# Schematic_Rev1.net
KiCad netlist of a schematic drawn in Altium Designer
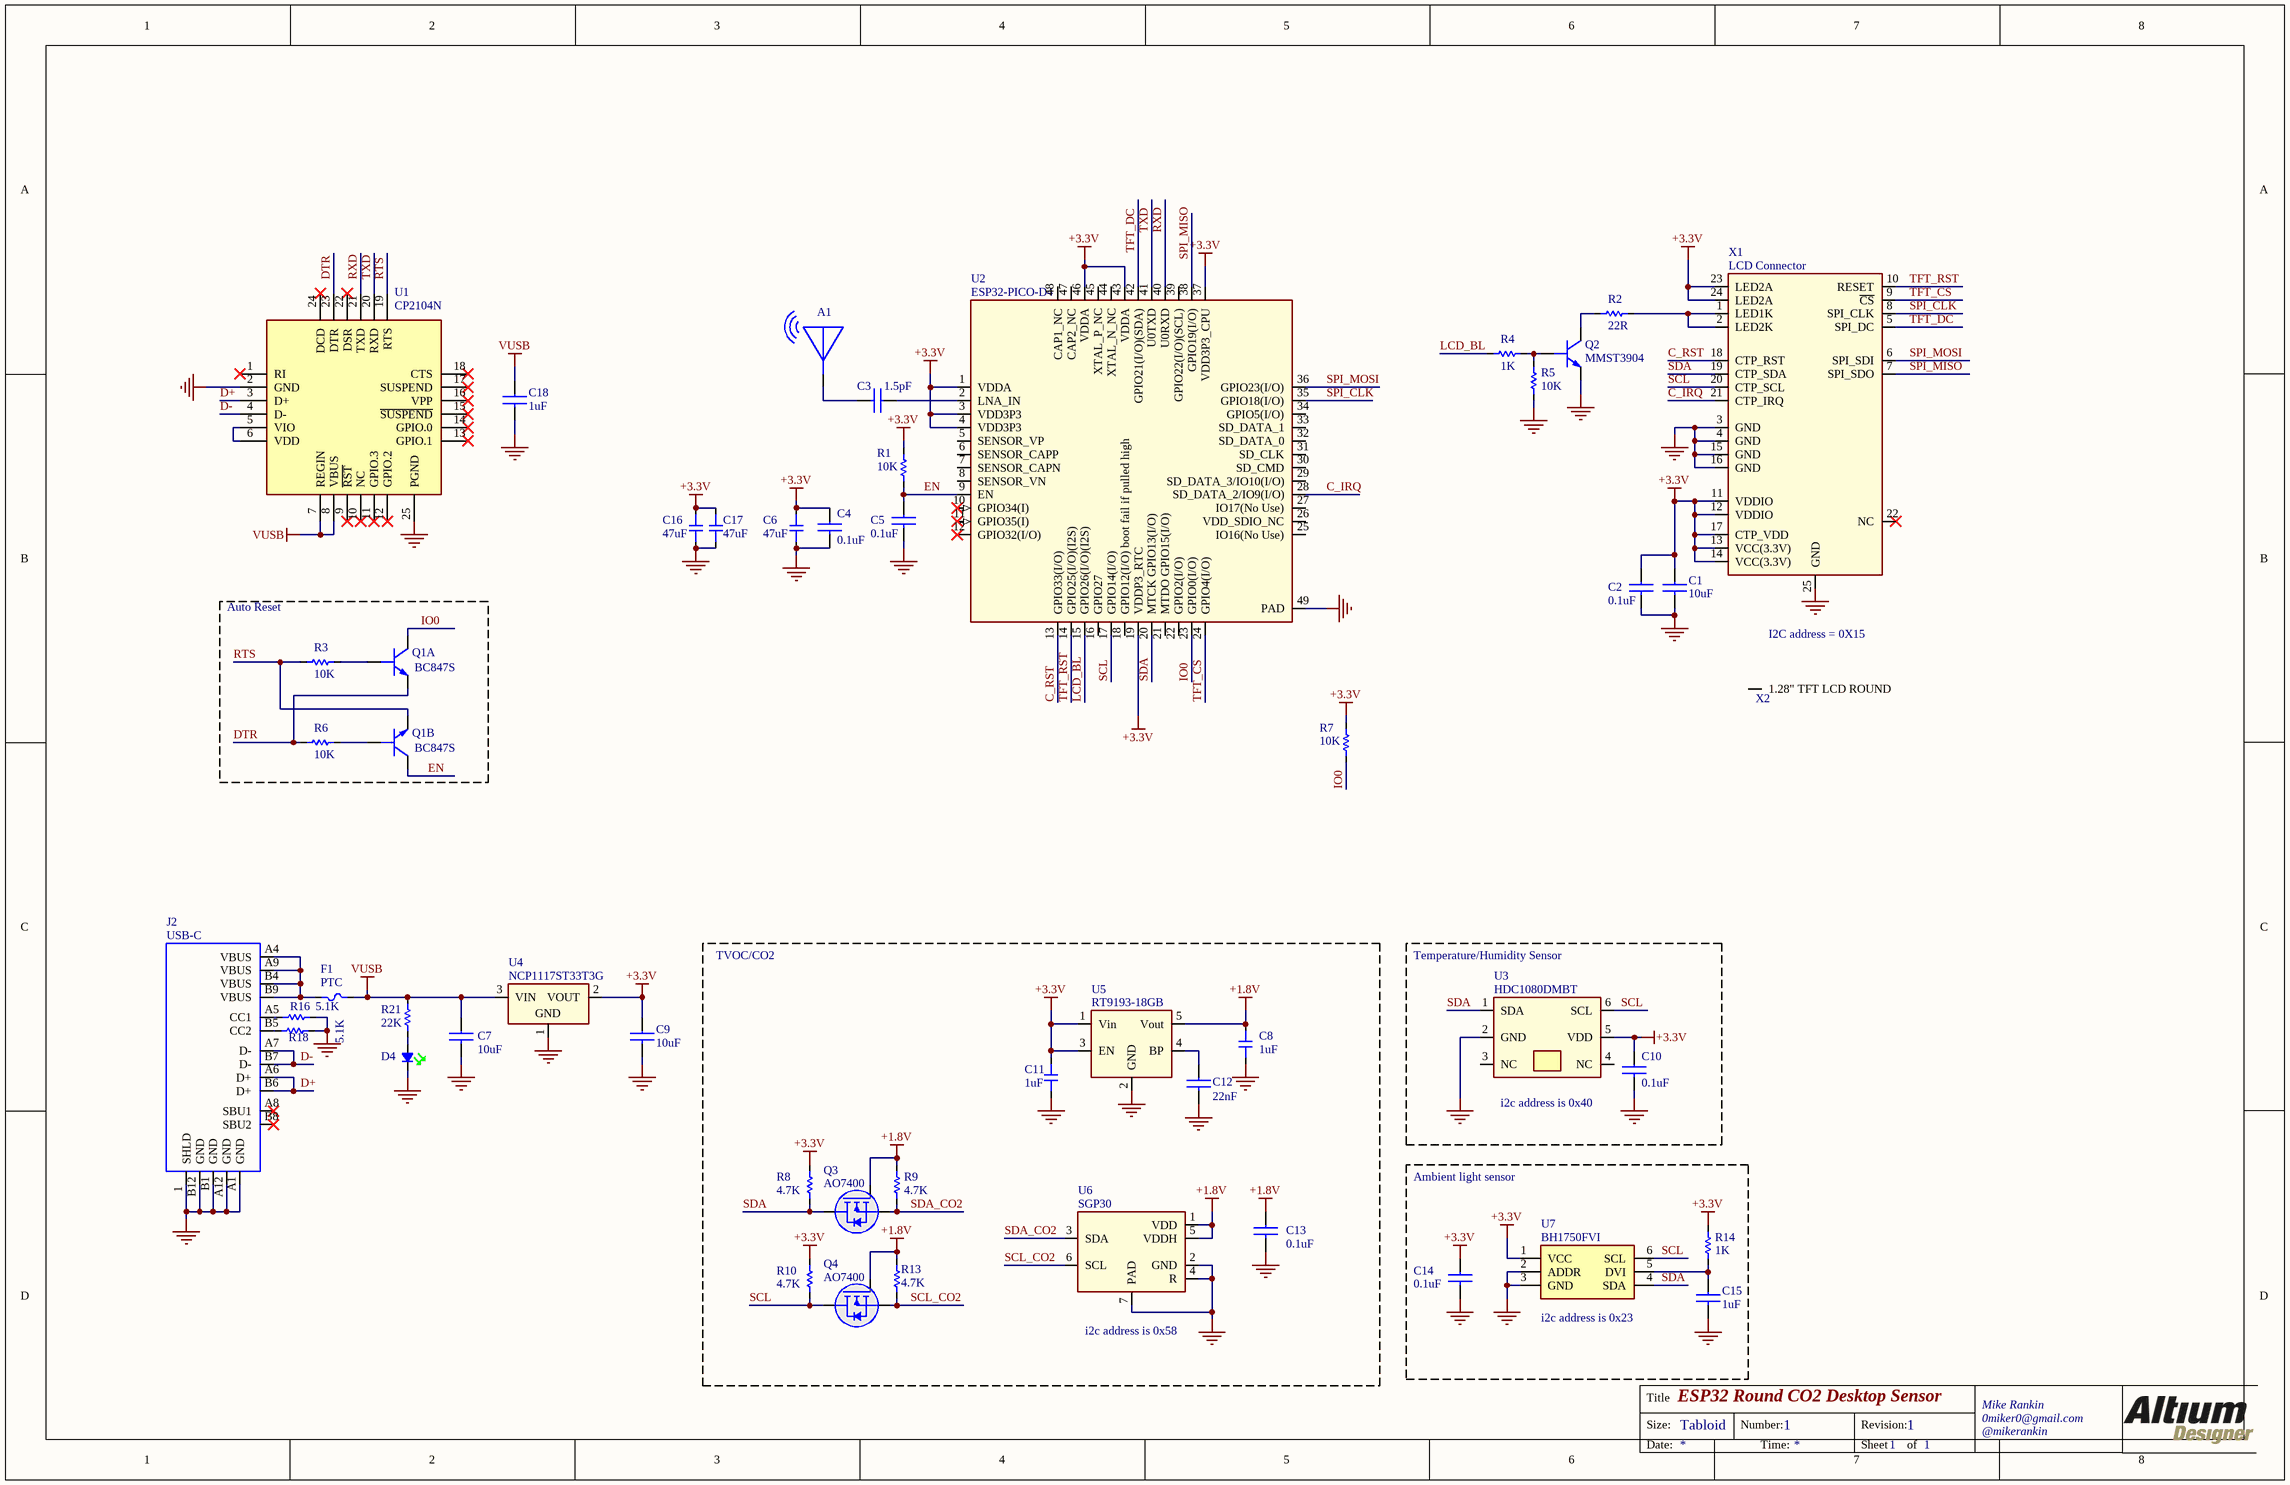
[diagram p0: Schematic_Rev1.SchDoc]

(export (version "E")
  (design (tool "Eeschema 10.0.6"))
  (components
    (comp (ref "A1")
      (value "Antenna_Chip_1")
      (footprint "NN01-102")
      (description "Antenna Chip 2.4Gig")
      (fields (field (name "MANUFACTURER") "Rainsun") (field (name "PART_NUMBER") "C99665"))
      (libsource (lib "MAR") (part "Antenna_Chip_1"))
    )
    (comp (ref "C1")
      (value "10uF")
      (footprint "CAPC2012X140N")
      (description "CAP 10uF 0805")
      (libsource (lib "MAR") (part "CAP_0805"))
    )
    (comp (ref "C2")
      (value "0.1uF")
      (footprint "CAPC1005X56N")
      (description "CAP 0.1uF 0402")
      (libsource (lib "MAR") (part "CAP_0402"))
    )
    (comp (ref "C3")
      (value "1.5pF")
      (footprint "CAPC1005X56N")
      (description "CAP 1.5pF 0402")
      (libsource (lib "MAR") (part "CAP_0402"))
    )
    (comp (ref "C4")
      (value "0.1uF")
      (footprint "CAPC1005X56N")
      (description "CAP 0.1uF 0402")
      (libsource (lib "MAR") (part "CAP_0402"))
    )
    (comp (ref "C5")
      (value "0.1uF")
      (footprint "CAPC1005X56N")
      (description "CAP 0.1uF 0402")
      (libsource (lib "MAR") (part "CAP_0402"))
    )
    (comp (ref "C6")
      (value "47uF")
      (footprint "CAPC3225X160N")
      (description "CAP 47uF 1210")
      (libsource (lib "MAR") (part "CAP_1210"))
    )
    (comp (ref "C7")
      (value "10uF")
      (footprint "CAPC2012X140N")
      (description "CAP 10uF 0805")
      (libsource (lib "MAR") (part "CAP_0805"))
    )
    (comp (ref "C8")
      (value "1uF")
      (footprint "CAPC1608X09L")
      (description "CAP 1uF 0603")
      (libsource (lib "MAR") (part "CAP_0603"))
    )
    (comp (ref "C9")
      (value "10uF")
      (footprint "CAPC2012X140N")
      (description "CAP 10uF 0805")
      (libsource (lib "MAR") (part "CAP_0805"))
    )
    (comp (ref "C10")
      (value "0.1uF")
      (footprint "CAPC1005X56N")
      (description "CAP 0.1uF 0402")
      (libsource (lib "MAR") (part "CAP_0402"))
    )
    (comp (ref "C11")
      (value "1uF")
      (footprint "CAPC1608X09L")
      (description "CAP 1uF 0603")
      (libsource (lib "MAR") (part "CAP_0603"))
    )
    (comp (ref "C12")
      (value "22nF")
      (footprint "CAPC1005X56N")
      (description "CAP 22nF 0402")
      (libsource (lib "MAR") (part "CAP_0402"))
    )
    (comp (ref "C13")
      (value "0.1uF")
      (footprint "CAPC1005X56N")
      (description "CAP 0.1uF 0402")
      (libsource (lib "MAR") (part "CAP_0402"))
    )
    (comp (ref "C14")
      (value "0.1uF")
      (footprint "CAPC1005X56N")
      (description "CAP 0.1uF 0402")
      (libsource (lib "MAR") (part "CAP_0402"))
    )
    (comp (ref "C15")
      (value "1uF")
      (footprint "CAPC1005X56N")
      (description "CAP 1uF 16V 0402")
      (libsource (lib "") (part "CAP_0603_1"))
    )
    (comp (ref "C16")
      (value "47uF")
      (footprint "CAPC3225X160N")
      (description "CAP 47uF 1210")
      (libsource (lib "MAR") (part "CAP_1210"))
    )
    (comp (ref "C17")
      (value "47uF")
      (footprint "CAPC3225X160N")
      (description "CAP 47uF 1210")
      (libsource (lib "MAR") (part "CAP_1210"))
    )
    (comp (ref "C18")
      (value "1uF")
      (footprint "CAPC1005X56N")
      (description "CAP 1uF 16V 0402")
      (libsource (lib "") (part "CAP_0603_1"))
    )
    (comp (ref "D4")
      (value "Green Led")
      (footprint "LED1005X40N-Green")
      (description "LED Green 0402")
      (fields (field (name "PART_NUMBER") "C74338"))
      (libsource (lib "MAR") (part "LED_0402_SMALL_GREEN"))
    )
    (comp (ref "F1")
      (value "PTC")
      (footprint "RESC1608X06L (0603 FOOTPRINT)")
      (description "PTC FUSE 0.5mA hold, 1A trip 0603")
      (fields (field (name "MANUFACTURER") "JDT Fuse") (field (name "PART_NUMBER") "C2982257"))
      (libsource (lib "MAR") (part "PTC_FUSE_0603"))
    )
    (comp (ref "J2")
      (value "USB-C")
      (footprint "TYPE-C-31-M-12")
      (description "CONN RECPT USB-C")
      (fields (field (name "MANUFACTURER") "KHE") (field (name "PART_NUMBER") "C165948"))
      (libsource (lib "MAR") (part "USB-C"))
    )
    (comp (ref "Q1")
      (value "BC847S")
      (footprint "SOT65P210X110-6N")
      (description "TRANS 2NPN 44V 0.1A SC-70-6")
      (fields (field (name "MANUFACTURER") "Changjiang") (field (name "PART_NUMBER") "BC847S"))
      (libsource (lib "MAR") (part "BC847S"))
    )
    (comp (ref "Q2")
      (value "MMST3904")
      (footprint "SC-70")
      (description "TRANSISTOR NPN GP 40V SC-70")
      (fields (field (name "MANUFACTURER") "Changjiang") (field (name "PART_NUMBER") "C54879"))
      (libsource (lib "MAR") (part "MMST3904"))
    )
    (comp (ref "Q3")
      (value "AO7400")
      (footprint "SC-70")
      (description "MOSFET N-CH 20V 4A SC70-3")
      (fields (field (name "MANUFACTURER") "VBSemi Elec"))
      (libsource (lib "MAR") (part "AO7400"))
    )
    (comp (ref "Q4")
      (value "AO7400")
      (footprint "SC-70")
      (description "MOSFET N-CH 20V 4A SC70-3")
      (fields (field (name "MANUFACTURER") "VBSemi Elec"))
      (libsource (lib "MAR") (part "AO7400"))
    )
    (comp (ref "R1")
      (value "10K")
      (footprint "RESC1005X40L")
      (description "RES 10K 0402")
      (libsource (lib "MAR") (part "RES_0402"))
    )
    (comp (ref "R2")
      (value "22R")
      (footprint "RESC1005X40L")
      (description "RES 22R 0402")
      (libsource (lib "MAR") (part "RES_0402"))
    )
    (comp (ref "R3")
      (value "10K")
      (footprint "RESC1005X40L")
      (description "RES 10K 0402")
      (libsource (lib "MAR") (part "RES_0402"))
    )
    (comp (ref "R4")
      (value "1K")
      (footprint "RESC1005X40L")
      (description "RES 1K 0402")
      (libsource (lib "MAR") (part "RES_0402"))
    )
    (comp (ref "R5")
      (value "10K")
      (footprint "RESC1005X40L")
      (description "RES 10K 0402")
      (libsource (lib "MAR") (part "RES_0402"))
    )
    (comp (ref "R6")
      (value "10K")
      (footprint "RESC1005X40L")
      (description "RES 10K 0402")
      (libsource (lib "MAR") (part "RES_0402"))
    )
    (comp (ref "R7")
      (value "10K")
      (footprint "RESC1005X40L")
      (description "RES 10K 0402")
      (libsource (lib "MAR") (part "RES_0402"))
    )
    (comp (ref "R8")
      (value "4.7K")
      (footprint "RESC1005X40L (0402 FOOTPRINT)")
      (description "RES 4.7K 0402")
      (libsource (lib "MAR") (part "RES_0402"))
    )
    (comp (ref "R9")
      (value "4.7K")
      (footprint "RESC1005X40L (0402 FOOTPRINT)")
      (description "RES 4.7K 0402")
      (libsource (lib "MAR") (part "RES_0402"))
    )
    (comp (ref "R10")
      (value "4.7K")
      (footprint "RESC1005X40L (0402 FOOTPRINT)")
      (description "RES 4.7K 0402")
      (libsource (lib "MAR") (part "RES_0402"))
    )
    (comp (ref "R13")
      (value "4.7K")
      (footprint "RESC1005X40L (0402 FOOTPRINT)")
      (description "RES 4.7K 0402")
      (libsource (lib "MAR") (part "RES_0402"))
    )
    (comp (ref "R14")
      (value "1K")
      (footprint "RESC1005X40L (0402 FOOTPRINT)")
      (description "RES 1K 0402")
      (libsource (lib "MAR") (part "RES_0402"))
    )
    (comp (ref "R16")
      (value "5.1K")
      (footprint "RESC1005X40L")
      (description "RES 5.1K 0402")
      (libsource (lib "MAR") (part "RES_0603"))
    )
    (comp (ref "R18")
      (value "5.1K")
      (footprint "RESC1005X40L")
      (description "RES 5.1K 0402")
      (libsource (lib "MAR") (part "RES_0603"))
    )
    (comp (ref "R21")
      (value "22K")
      (footprint "RESC1005X40L")
      (description "RES 22K 0402")
      (libsource (lib "MAR") (part "RES_0603"))
    )
    (comp (ref "U1")
      (value "CP2104N")
      (footprint "24-QFN")
      (description "IC BRIDGE USB TO UART 24QFN")
      (fields (field (name "MANUFACTURER") "Silicon Labs") (field (name "PART_NUMBER") "C47742"))
      (libsource (lib "MAR") (part "CP2104N"))
    )
    (comp (ref "U2")
      (value "ESP32-PICO-D4")
      (footprint "QFN48_NEWEST 0.5mm pitch")
      (description "WIFI/Bluetooth, QFN-48 7x7")
      (fields (field (name "MANUFACTURER") "Espressif") (field (name "PART_NUMBER") "C193707"))
      (libsource (lib "MAR") (part "ESP32-PICO-D4"))
    )
    (comp (ref "U3")
      (value "HDC1080DMBT")
      (footprint "HDC1080")
      (description "Humidity/Temperature Sensor")
      (fields (field (name "MANUFACTURER") "Texas Instruments") (field (name "PART_NUMBER") "C82227"))
      (libsource (lib "MAR") (part "HDC1080DMBT"))
    )
    (comp (ref "U4")
      (value "NCP1117ST33T3G")
      (footprint "SOT230P700X180-4N")
      (description "IC REG LDO 1.0A 3.3V SOT-223")
      (fields (field (name "MANUFACTURER") "On Semi") (field (name "PART_NUMBER") "C26537"))
      (libsource (lib "MAR") (part "NCP1117ST33T3G"))
    )
    (comp (ref "U5")
      (value "1.8V LDO")
      (footprint "SOT95P280X144-5N")
      (description "IC REG LDO 1.8V 300mA SOT23-5")
      (fields (field (name "MANUFACTURER") "Richtek USA") (field (name "PART_NUMBER") "RT9193-18GB"))
      (libsource (lib "MAR") (part "RT9193-18GB"))
    )
    (comp (ref "U6")
      (value "SGP30")
      (footprint "DFN-6 (2.45mm X 2.45mm)")
      (description "TVOC/CO2 Sensor")
      (fields (field (name "MANUFACTURER") "Sensirion AG") (field (name "PART_NUMBER") "SGP30-2.5K"))
      (libsource (lib "MAR") (part "SGP30"))
    )
    (comp (ref "U7")
      (value "BH1750FVI")
      (footprint "WSOF-6")
      (description "Optical Sensor Ambient I2C 6-SMD")
      (fields (field (name "MANUFACTURER") "Rohm") (field (name "PART_NUMBER") "C78960"))
      (libsource (lib "MAR") (part "BH1750FVI"))
    )
    (comp (ref "X1")
      (value "LCD Connector")
      (footprint "BM10NB(0.8)-24DS-0.4V(51)")
      (description "FFC, FPC 24 pin 0.4mm Connector for 1.28\" TFT")
      (fields (field (name "PART_NUMBER") "BM10NB(0.8)-24DS-0.4V(51)") (field (name "MANUFACTURER") "Hirose"))
      (libsource (lib "MAR") (part "FFC, FPC 24 pin 0.5mm Con 1.28{dblquote} TFT"))
    )
    (comp (ref "X2")
      (value "TFT_1.28 inch")
      (description "1.28 INCH TFT GLASS ROUND")
      (fields (field (name "PART_NUMBER") "ER-TFT1.28-2") (field (name "MANUFACTURER") "BuyDisplay"))
      (libsource (lib "MAR") (part "TFT_GLASS 1.28 Inch Round"))
    )
  )
  (nets
    (net (code "1") (name "+1.8V") (class "Default")
      (node (ref "C13") (pin "1") (pinfunction "1_1") (pintype "passive"))
      (node (ref "C8") (pin "1") (pintype "passive"))
      (node (ref "Q3") (pin "1") (pinfunction "G_1") (pintype "passive"))
      (node (ref "Q4") (pin "1") (pinfunction "G_1") (pintype "passive"))
      (node (ref "R13") (pin "2") (pintype "passive"))
      (node (ref "R9") (pin "2") (pintype "passive"))
      (node (ref "U5") (pin "5") (pinfunction "Vout_5") (pintype "passive"))
      (node (ref "U6") (pin "1") (pinfunction "VDD_1") (pintype "power_in"))
      (node (ref "U6") (pin "5") (pinfunction "VDDH_5") (pintype "power_in"))
    )
    (net (code "2") (name "+3.3V") (class "Default")
      (node (ref "C1") (pin "1") (pinfunction "1_1") (pintype "passive"))
      (node (ref "C10") (pin "1") (pinfunction "1_1") (pintype "passive"))
      (node (ref "C11") (pin "1") (pintype "passive"))
      (node (ref "C14") (pin "1") (pinfunction "1_1") (pintype "passive"))
      (node (ref "C16") (pin "1") (pintype "passive"))
      (node (ref "C17") (pin "1") (pintype "passive"))
      (node (ref "C2") (pin "1") (pinfunction "1_1") (pintype "passive"))
      (node (ref "C4") (pin "1") (pinfunction "1_1") (pintype "passive"))
      (node (ref "C6") (pin "1") (pintype "passive"))
      (node (ref "C9") (pin "1") (pinfunction "1_1") (pintype "passive"))
      (node (ref "R1") (pin "1") (pintype "passive"))
      (node (ref "R10") (pin "2") (pintype "passive"))
      (node (ref "R14") (pin "2") (pintype "passive"))
      (node (ref "R7") (pin "1") (pintype "passive"))
      (node (ref "R8") (pin "2") (pintype "passive"))
      (node (ref "U2") (pin "1") (pinfunction "VDDA_1") (pintype "power_in"))
      (node (ref "U2") (pin "19") (pinfunction "VDDP3_RTC_19") (pintype "passive"))
      (node (ref "U2") (pin "3") (pinfunction "VDD3P3_3") (pintype "power_in"))
      (node (ref "U2") (pin "37") (pinfunction "VDD3P3_CPU_37") (pintype "power_in"))
      (node (ref "U2") (pin "4") (pinfunction "VDD3P3_4") (pintype "power_in"))
      (node (ref "U2") (pin "43") (pinfunction "VDDA_43") (pintype "power_in"))
      (node (ref "U2") (pin "46") (pinfunction "VDDA_46") (pintype "power_in"))
      (node (ref "U3") (pin "5") (pinfunction "VDD_5") (pintype "power_in"))
      (node (ref "U4") (pin "2") (pinfunction "VOUT_2") (pintype "power_in"))
      (node (ref "U5") (pin "1") (pinfunction "Vin_1") (pintype "passive"))
      (node (ref "U5") (pin "3") (pinfunction "EN_3") (pintype "passive"))
      (node (ref "U7") (pin "1") (pinfunction "VCC_1") (pintype "power_in"))
      (node (ref "X1") (pin "11") (pinfunction "VDDIO_11") (pintype "power_in"))
      (node (ref "X1") (pin "12") (pinfunction "VDDIO_12") (pintype "power_in"))
      (node (ref "X1") (pin "13") (pinfunction "VCC(3.3V)_13") (pintype "power_in"))
      (node (ref "X1") (pin "14") (pinfunction "VCC(3.3V)_14") (pintype "open_emitter"))
      (node (ref "X1") (pin "17") (pinfunction "CTP_VDD_17") (pintype "power_in"))
      (node (ref "X1") (pin "23") (pinfunction "LED2A_23") (pintype "passive"))
      (node (ref "X1") (pin "24") (pinfunction "LED2A_24") (pintype "passive"))
    )
    (net (code "3") (name "/C_IRQ") (class "Default")
      (node (ref "U2") (pin "28") (pinfunction "SD_DATA_2/IO9(I/O)_28") (pintype "passive"))
      (node (ref "X1") (pin "21") (pinfunction "CTP_IRQ_21") (pintype "passive"))
    )
    (net (code "4") (name "/C_RST") (class "Default")
      (node (ref "U2") (pin "13") (pinfunction "GPIO33(I/O)_13") (pintype "passive"))
      (node (ref "X1") (pin "18") (pinfunction "CTP_RST_18") (pintype "passive"))
    )
    (net (code "5") (name "/D+") (class "Default")
      (node (ref "J2") (pin "A6") (pinfunction "D+_A6") (pintype "power_in"))
      (node (ref "J2") (pin "B6") (pinfunction "D+_B6") (pintype "power_in"))
      (node (ref "U1") (pin "3") (pinfunction "D+_3") (pintype "passive"))
    )
    (net (code "6") (name "/D-") (class "Default")
      (node (ref "J2") (pin "A7") (pinfunction "D-_A7") (pintype "power_in"))
      (node (ref "J2") (pin "B7") (pinfunction "D-_B7") (pintype "power_in"))
      (node (ref "U1") (pin "4") (pinfunction "D-_4") (pintype "passive"))
    )
    (net (code "7") (name "/DTR") (class "Default")
      (node (ref "Q1") (pin "1") (pinfunction "E1_1") (pintype "passive"))
      (node (ref "R6") (pin "2") (pintype "passive"))
      (node (ref "U1") (pin "23") (pinfunction "DTR_23") (pintype "passive"))
    )
    (net (code "8") (name "/EN") (class "Default")
      (node (ref "C5") (pin "1") (pinfunction "1_1") (pintype "passive"))
      (node (ref "Q1") (pin "3") (pinfunction "C2_3") (pintype "passive"))
      (node (ref "R1") (pin "2") (pintype "passive"))
      (node (ref "U2") (pin "9") (pinfunction "EN_9") (pintype "passive"))
    )
    (net (code "9") (name "/IO0") (class "Default")
      (node (ref "Q1") (pin "6") (pinfunction "C1_6") (pintype "passive"))
      (node (ref "R7") (pin "2") (pintype "passive"))
      (node (ref "U2") (pin "23") (pinfunction "GPIO0(I/O)_23") (pintype "passive"))
    )
    (net (code "10") (name "/LCD_BL") (class "Default")
      (node (ref "R4") (pin "1") (pintype "passive"))
      (node (ref "U2") (pin "15") (pinfunction "GPIO26(I/O)(I2S)_15") (pintype "passive"))
    )
    (net (code "11") (name "/RTS") (class "Default")
      (node (ref "Q1") (pin "4") (pinfunction "E2_4") (pintype "passive"))
      (node (ref "R3") (pin "2") (pintype "passive"))
      (node (ref "U1") (pin "19") (pinfunction "RTS_19") (pintype "passive"))
    )
    (net (code "12") (name "/RXD") (class "Default")
      (node (ref "U1") (pin "21") (pinfunction "TXD_21") (pintype "passive"))
      (node (ref "U2") (pin "40") (pinfunction "U0RXD_40") (pintype "passive"))
    )
    (net (code "13") (name "/SCL") (class "Default")
      (node (ref "Q4") (pin "3") (pinfunction "D_3") (pintype "passive"))
      (node (ref "R10") (pin "1") (pintype "passive"))
      (node (ref "U2") (pin "17") (pinfunction "GPIO14(I/O)_17") (pintype "passive"))
      (node (ref "U3") (pin "6") (pinfunction "SCL_6") (pintype "passive"))
      (node (ref "U7") (pin "6") (pinfunction "SCL_6") (pintype "passive"))
      (node (ref "X1") (pin "20") (pinfunction "CTP_SCL_20") (pintype "passive"))
    )
    (net (code "14") (name "/SCL_CO2") (class "Default")
      (node (ref "Q4") (pin "2") (pinfunction "S_2") (pintype "passive"))
      (node (ref "R13") (pin "1") (pintype "passive"))
      (node (ref "U6") (pin "6") (pinfunction "SCL_6") (pintype "passive"))
    )
    (net (code "15") (name "/SDA") (class "Default")
      (node (ref "Q3") (pin "3") (pinfunction "D_3") (pintype "passive"))
      (node (ref "R8") (pin "1") (pintype "passive"))
      (node (ref "U2") (pin "20") (pinfunction "MTCK_GPIO13(I/O)_20") (pintype "passive"))
      (node (ref "U3") (pin "1") (pinfunction "SDA_1") (pintype "passive"))
      (node (ref "U7") (pin "4") (pinfunction "SDA_4") (pintype "passive"))
      (node (ref "X1") (pin "19") (pinfunction "CTP_SDA_19") (pintype "passive"))
    )
    (net (code "16") (name "/SDA_CO2") (class "Default")
      (node (ref "Q3") (pin "2") (pinfunction "S_2") (pintype "passive"))
      (node (ref "R9") (pin "1") (pintype "passive"))
      (node (ref "U6") (pin "3") (pinfunction "SDA_3") (pintype "passive"))
    )
    (net (code "17") (name "/SPI_CLK") (class "Default")
      (node (ref "U2") (pin "35") (pinfunction "GPIO18(I/O)_35") (pintype "passive"))
      (node (ref "X1") (pin "8") (pinfunction "SPI_CLK_8") (pintype "passive"))
    )
    (net (code "18") (name "/SPI_MISO") (class "Default")
      (node (ref "U2") (pin "38") (pinfunction "GPIO19(I/O)_38") (pintype "passive"))
      (node (ref "X1") (pin "7") (pinfunction "SPI_SDO_7") (pintype "passive"))
    )
    (net (code "19") (name "/SPI_MOSI") (class "Default")
      (node (ref "U2") (pin "36") (pinfunction "GPIO23(I/O)_36") (pintype "passive"))
      (node (ref "X1") (pin "6") (pinfunction "SPI_SDI_6") (pintype "passive"))
    )
    (net (code "20") (name "/TFT_CS") (class "Default")
      (node (ref "U2") (pin "24") (pinfunction "GPIO4(I/O)_24") (pintype "passive"))
      (node (ref "X1") (pin "9") (pinfunction "~{CS}_9") (pintype "passive"))
    )
    (net (code "21") (name "/TFT_DC") (class "Default")
      (node (ref "U2") (pin "42") (pinfunction "GPIO21(I/O)(SDA)_42") (pintype "passive"))
      (node (ref "X1") (pin "5") (pinfunction "SPI_DC_5") (pintype "passive"))
    )
    (net (code "22") (name "/TFT_RST") (class "Default")
      (node (ref "U2") (pin "14") (pinfunction "GPIO25(I/O)(I2S)_14") (pintype "passive"))
      (node (ref "X1") (pin "10") (pinfunction "RESET_10") (pintype "passive"))
    )
    (net (code "23") (name "/TXD") (class "Default")
      (node (ref "U1") (pin "20") (pinfunction "RXD_20") (pintype "passive"))
      (node (ref "U2") (pin "41") (pinfunction "U0TXD_41") (pintype "passive"))
    )
    (net (code "24") (name "GND") (class "Default")
      (node (ref "C1") (pin "2") (pinfunction "2_2") (pintype "passive"))
      (node (ref "C10") (pin "2") (pinfunction "2_2") (pintype "passive"))
      (node (ref "C11") (pin "2") (pintype "passive"))
      (node (ref "C12") (pin "2") (pinfunction "2_2") (pintype "passive"))
      (node (ref "C13") (pin "2") (pinfunction "2_2") (pintype "passive"))
      (node (ref "C14") (pin "2") (pinfunction "2_2") (pintype "passive"))
      (node (ref "C15") (pin "2") (pinfunction "2_2") (pintype "passive"))
      (node (ref "C16") (pin "2") (pintype "passive"))
      (node (ref "C17") (pin "2") (pintype "passive"))
      (node (ref "C18") (pin "2") (pinfunction "2_2") (pintype "passive"))
      (node (ref "C2") (pin "2") (pinfunction "2_2") (pintype "passive"))
      (node (ref "C4") (pin "2") (pinfunction "2_2") (pintype "passive"))
      (node (ref "C5") (pin "2") (pinfunction "2_2") (pintype "passive"))
      (node (ref "C6") (pin "2") (pintype "passive"))
      (node (ref "C7") (pin "2") (pinfunction "2_2") (pintype "passive"))
      (node (ref "C8") (pin "2") (pintype "passive"))
      (node (ref "C9") (pin "2") (pinfunction "2_2") (pintype "passive"))
      (node (ref "D4") (pin "1") (pintype "passive"))
      (node (ref "J2") (pin "1") (pinfunction "SHLD_1") (pintype "power_in"))
      (node (ref "J2") (pin "A1") (pinfunction "GND_A1") (pintype "power_in"))
      (node (ref "J2") (pin "A12") (pinfunction "GND_A12") (pintype "power_in"))
      (node (ref "J2") (pin "B1") (pinfunction "GND_B1") (pintype "power_in"))
      (node (ref "J2") (pin "B12") (pinfunction "GND_B12") (pintype "passive"))
      (node (ref "Q2") (pin "2") (pinfunction "E_2") (pintype "passive"))
      (node (ref "R16") (pin "2") (pintype "passive"))
      (node (ref "R18") (pin "2") (pintype "passive"))
      (node (ref "R5") (pin "2") (pintype "passive"))
      (node (ref "U1") (pin "2") (pinfunction "GND_2") (pintype "power_in"))
      (node (ref "U1") (pin "25") (pinfunction "PGND_25") (pintype "passive"))
      (node (ref "U2") (pin "49") (pinfunction "PAD_49") (pintype "power_in"))
      (node (ref "U3") (pin "2") (pinfunction "GND_2") (pintype "power_in"))
      (node (ref "U4") (pin "1") (pinfunction "GND_1") (pintype "power_in"))
      (node (ref "U5") (pin "2") (pinfunction "GND_2") (pintype "power_in"))
      (node (ref "U6") (pin "2") (pinfunction "GND_2") (pintype "power_in"))
      (node (ref "U6") (pin "4") (pinfunction "R_4") (pintype "passive"))
      (node (ref "U6") (pin "7") (pinfunction "PAD_7") (pintype "passive"))
      (node (ref "U7") (pin "2") (pinfunction "ADDR_2") (pintype "passive"))
      (node (ref "U7") (pin "3") (pinfunction "GND_3") (pintype "power_in"))
      (node (ref "X1") (pin "15") (pinfunction "GND_15") (pintype "power_in"))
      (node (ref "X1") (pin "16") (pinfunction "GND_16") (pintype "power_in"))
      (node (ref "X1") (pin "25") (pinfunction "GND_25") (pintype "power_in"))
      (node (ref "X1") (pin "3") (pinfunction "GND_3") (pintype "power_in"))
      (node (ref "X1") (pin "4") (pinfunction "GND_4") (pintype "power_in"))
    )
    (net (code "25") (name "Net-(A1-Pad1)") (class "Default")
      (node (ref "A1") (pin "1") (pintype "passive"))
      (node (ref "C3") (pin "2") (pinfunction "2_2") (pintype "passive"))
    )
    (net (code "26") (name "Net-(D4-Pad2)") (class "Default")
      (node (ref "D4") (pin "2") (pintype "passive"))
      (node (ref "R21") (pin "1") (pintype "passive"))
    )
    (net (code "27") (name "Net-(F1-Pad2)") (class "Default")
      (node (ref "F1") (pin "2") (pintype "passive"))
      (node (ref "J2") (pin "A4") (pinfunction "VBUS_A4") (pintype "passive"))
      (node (ref "J2") (pin "A9") (pinfunction "VBUS_A9") (pintype "power_in"))
      (node (ref "J2") (pin "B4") (pinfunction "VBUS_B4") (pintype "power_in"))
      (node (ref "J2") (pin "B9") (pinfunction "VBUS_B9") (pintype "passive"))
    )
    (net (code "28") (name "Net-(J2-CC1)") (class "Default")
      (node (ref "J2") (pin "A5") (pinfunction "CC1_A5") (pintype "power_in"))
      (node (ref "R16") (pin "1") (pintype "passive"))
    )
    (net (code "29") (name "Net-(J2-CC2)") (class "Default")
      (node (ref "J2") (pin "B5") (pinfunction "CC2_B5") (pintype "power_in"))
      (node (ref "R18") (pin "1") (pintype "passive"))
    )
    (net (code "30") (name "Net-(Q1A-B1)") (class "Default")
      (node (ref "Q1") (pin "2") (pinfunction "B1_2") (pintype "passive"))
      (node (ref "R3") (pin "1") (pintype "passive"))
    )
    (net (code "31") (name "Net-(Q1B-B2)") (class "Default")
      (node (ref "Q1") (pin "5") (pinfunction "B2_5") (pintype "passive"))
      (node (ref "R6") (pin "1") (pintype "passive"))
    )
    (net (code "32") (name "Net-(Q2-B)") (class "Default")
      (node (ref "Q2") (pin "1") (pinfunction "B_1") (pintype "passive"))
      (node (ref "R4") (pin "2") (pintype "passive"))
      (node (ref "R5") (pin "1") (pintype "passive"))
    )
    (net (code "33") (name "Net-(Q2-C)") (class "Default")
      (node (ref "Q2") (pin "3") (pinfunction "C_3") (pintype "passive"))
      (node (ref "R2") (pin "2") (pintype "passive"))
    )
    (net (code "34") (name "Net-(U1-VDD)") (class "Default")
      (node (ref "U1") (pin "5") (pinfunction "VIO_5") (pintype "power_in"))
      (node (ref "U1") (pin "6") (pinfunction "VDD_6") (pintype "power_in"))
    )
    (net (code "35") (name "Net-(U2-LNA_IN)") (class "Default")
      (node (ref "C3") (pin "1") (pinfunction "1_1") (pintype "passive"))
      (node (ref "U2") (pin "2") (pinfunction "LNA_IN_2") (pintype "passive"))
    )
    (net (code "36") (name "Net-(U5-BP)") (class "Default")
      (node (ref "C12") (pin "1") (pinfunction "1_1") (pintype "passive"))
      (node (ref "U5") (pin "4") (pinfunction "BP_4") (pintype "passive"))
    )
    (net (code "37") (name "Net-(U7-DVI)") (class "Default")
      (node (ref "C15") (pin "1") (pinfunction "1_1") (pintype "passive"))
      (node (ref "R14") (pin "1") (pintype "passive"))
      (node (ref "U7") (pin "5") (pinfunction "DVI_5") (pintype "passive"))
    )
    (net (code "38") (name "Net-(X1-LED1K)") (class "Default")
      (node (ref "R2") (pin "1") (pintype "passive"))
      (node (ref "X1") (pin "1") (pinfunction "LED1K_1") (pintype "passive"))
      (node (ref "X1") (pin "2") (pinfunction "LED2K_2") (pintype "passive"))
    )
    (net (code "39") (name "VUSB") (class "Default")
      (node (ref "C18") (pin "1") (pinfunction "1_1") (pintype "passive"))
      (node (ref "C7") (pin "1") (pinfunction "1_1") (pintype "passive"))
      (node (ref "F1") (pin "1") (pintype "passive"))
      (node (ref "R21") (pin "2") (pintype "passive"))
      (node (ref "U1") (pin "7") (pinfunction "REGIN_7") (pintype "power_in"))
      (node (ref "U1") (pin "8") (pinfunction "VBUS_8") (pintype "power_in"))
      (node (ref "U4") (pin "3") (pinfunction "VIN_3") (pintype "power_in"))
    )
    (net (code "40") (name "unconnected-(J2-SBU1-PadA8)") (class "Default")
      (node (ref "J2") (pin "A8") (pinfunction "SBU1_A8") (pintype "power_in+no_connect"))
    )
    (net (code "41") (name "unconnected-(J2-SBU2-PadB8)") (class "Default")
      (node (ref "J2") (pin "B8") (pinfunction "SBU2_B8") (pintype "power_in+no_connect"))
    )
    (net (code "42") (name "unconnected-(U1-CTS-Pad18)") (class "Default")
      (node (ref "U1") (pin "18") (pinfunction "CTS_18") (pintype "passive+no_connect"))
    )
    (net (code "43") (name "unconnected-(U1-DCD-Pad24)") (class "Default")
      (node (ref "U1") (pin "24") (pinfunction "DCD_24") (pintype "passive+no_connect"))
    )
    (net (code "44") (name "unconnected-(U1-DSR-Pad22)") (class "Default")
      (node (ref "U1") (pin "22") (pinfunction "DSR_22") (pintype "passive+no_connect"))
    )
    (net (code "45") (name "unconnected-(U1-GPIO.0-Pad14)") (class "Default")
      (node (ref "U1") (pin "14") (pinfunction "GPIO.0_14") (pintype "passive+no_connect"))
    )
    (net (code "46") (name "unconnected-(U1-GPIO.1-Pad13)") (class "Default")
      (node (ref "U1") (pin "13") (pinfunction "GPIO.1_13") (pintype "passive+no_connect"))
    )
    (net (code "47") (name "unconnected-(U1-GPIO.2-Pad12)") (class "Default")
      (node (ref "U1") (pin "12") (pinfunction "GPIO.2_12") (pintype "passive+no_connect"))
    )
    (net (code "48") (name "unconnected-(U1-GPIO.3-Pad11)") (class "Default")
      (node (ref "U1") (pin "11") (pinfunction "GPIO.3_11") (pintype "passive+no_connect"))
    )
    (net (code "49") (name "unconnected-(U1-NC-Pad10)") (class "Default")
      (node (ref "U1") (pin "10") (pinfunction "NC_10") (pintype "passive+no_connect"))
    )
    (net (code "50") (name "unconnected-(U1-RI-Pad1)") (class "Default")
      (node (ref "U1") (pin "1") (pinfunction "RI_1") (pintype "passive+no_connect"))
    )
    (net (code "51") (name "unconnected-(U1-SUSPEND-Pad17)") (class "Default")
      (node (ref "U1") (pin "17") (pinfunction "SUSPEND_17") (pintype "passive+no_connect"))
    )
    (net (code "52") (name "unconnected-(U1-VPP-Pad16)") (class "Default")
      (node (ref "U1") (pin "16") (pinfunction "VPP_16") (pintype "passive+no_connect"))
    )
    (net (code "53") (name "unconnected-(U1-~{RST}-Pad9)") (class "Default")
      (node (ref "U1") (pin "9") (pinfunction "~{RST}_9") (pintype "passive+no_connect"))
    )
    (net (code "54") (name "unconnected-(U1-~{SUSPEND}-Pad15)") (class "Default")
      (node (ref "U1") (pin "15") (pinfunction "~{SUSPEND}_15") (pintype "passive+no_connect"))
    )
    (net (code "55") (name "unconnected-(U2-CAP1_NC-Pad48)") (class "Default")
      (node (ref "U2") (pin "48") (pinfunction "CAP1_NC_48") (pintype "passive"))
    )
    (net (code "56") (name "unconnected-(U2-CAP2_NC-Pad47)") (class "Default")
      (node (ref "U2") (pin "47") (pinfunction "CAP2_NC_47") (pintype "passive"))
    )
    (net (code "57") (name "unconnected-(U2-GPIO2(I{slash}O)-Pad22)") (class "Default")
      (node (ref "U2") (pin "22") (pinfunction "GPIO2(I/O)_22") (pintype "passive"))
    )
    (net (code "58") (name "unconnected-(U2-GPIO5(I{slash}O)-Pad34)") (class "Default")
      (node (ref "U2") (pin "34") (pinfunction "GPIO5(I/O)_34") (pintype "passive"))
    )
    (net (code "59") (name "unconnected-(U2-GPIO12(I{slash}O)_boot_fail_if_pulled_high-Pad18)") (class "Default")
      (node (ref "U2") (pin "18") (pinfunction "GPIO12(I/O)_boot_fail_if_pulled_high_18") (pintype "passive"))
    )
    (net (code "60") (name "unconnected-(U2-GPIO22(I{slash}O)(SCL)-Pad39)") (class "Default")
      (node (ref "U2") (pin "39") (pinfunction "GPIO22(I/O)(SCL)_39") (pintype "passive"))
    )
    (net (code "61") (name "unconnected-(U2-GPIO27-Pad16)") (class "Default")
      (node (ref "U2") (pin "16") (pinfunction "GPIO27_16") (pintype "passive"))
    )
    (net (code "62") (name "unconnected-(U2-GPIO32(I{slash}O)-Pad12)") (class "Default")
      (node (ref "U2") (pin "12") (pinfunction "GPIO32(I/O)_12") (pintype "passive+no_connect"))
    )
    (net (code "63") (name "unconnected-(U2-GPIO34(I)-Pad10)") (class "Default")
      (node (ref "U2") (pin "10") (pinfunction "GPIO34(I)_10") (pintype "input+no_connect"))
    )
    (net (code "64") (name "unconnected-(U2-GPIO35(I)-Pad11)") (class "Default")
      (node (ref "U2") (pin "11") (pinfunction "GPIO35(I)_11") (pintype "input+no_connect"))
    )
    (net (code "65") (name "unconnected-(U2-IO16(No_Use)-Pad25)") (class "Default")
      (node (ref "U2") (pin "25") (pinfunction "IO16(No_Use)_25") (pintype "passive"))
    )
    (net (code "66") (name "unconnected-(U2-IO17(No_Use)-Pad27)") (class "Default")
      (node (ref "U2") (pin "27") (pinfunction "IO17(No_Use)_27") (pintype "passive"))
    )
    (net (code "67") (name "unconnected-(U2-MTDO_GPIO15(I{slash}O)-Pad21)") (class "Default")
      (node (ref "U2") (pin "21") (pinfunction "MTDO_GPIO15(I/O)_21") (pintype "passive"))
    )
    (net (code "68") (name "unconnected-(U2-SD_CLK-Pad31)") (class "Default")
      (node (ref "U2") (pin "31") (pinfunction "SD_CLK_31") (pintype "passive"))
    )
    (net (code "69") (name "unconnected-(U2-SD_CMD-Pad30)") (class "Default")
      (node (ref "U2") (pin "30") (pinfunction "SD_CMD_30") (pintype "passive"))
    )
    (net (code "70") (name "unconnected-(U2-SD_DATA_0-Pad32)") (class "Default")
      (node (ref "U2") (pin "32") (pinfunction "SD_DATA_0_32") (pintype "passive"))
    )
    (net (code "71") (name "unconnected-(U2-SD_DATA_1-Pad33)") (class "Default")
      (node (ref "U2") (pin "33") (pinfunction "SD_DATA_1_33") (pintype "passive"))
    )
    (net (code "72") (name "unconnected-(U2-SD_DATA_3{slash}IO10(I{slash}O)-Pad29)") (class "Default")
      (node (ref "U2") (pin "29") (pinfunction "SD_DATA_3/IO10(I/O)_29") (pintype "passive"))
    )
    (net (code "73") (name "unconnected-(U2-SENSOR_CAPN-Pad7)") (class "Default")
      (node (ref "U2") (pin "7") (pinfunction "SENSOR_CAPN_7") (pintype "passive"))
    )
    (net (code "74") (name "unconnected-(U2-SENSOR_CAPP-Pad6)") (class "Default")
      (node (ref "U2") (pin "6") (pinfunction "SENSOR_CAPP_6") (pintype "passive"))
    )
    (net (code "75") (name "unconnected-(U2-SENSOR_VN-Pad8)") (class "Default")
      (node (ref "U2") (pin "8") (pinfunction "SENSOR_VN_8") (pintype "passive"))
    )
    (net (code "76") (name "unconnected-(U2-SENSOR_VP-Pad5)") (class "Default")
      (node (ref "U2") (pin "5") (pinfunction "SENSOR_VP_5") (pintype "passive"))
    )
    (net (code "77") (name "unconnected-(U2-VDD_SDIO_NC-Pad26)") (class "Default")
      (node (ref "U2") (pin "26") (pinfunction "VDD_SDIO_NC_26") (pintype "power_in"))
    )
    (net (code "78") (name "unconnected-(U2-XTAL_N_NC-Pad44)") (class "Default")
      (node (ref "U2") (pin "44") (pinfunction "XTAL_N_NC_44") (pintype "passive"))
    )
    (net (code "79") (name "unconnected-(U2-XTAL_P_NC-Pad45)") (class "Default")
      (node (ref "U2") (pin "45") (pinfunction "XTAL_P_NC_45") (pintype "passive"))
    )
    (net (code "80") (name "unconnected-(U3-NC-Pad3)") (class "Default")
      (node (ref "U3") (pin "3") (pinfunction "NC_3") (pintype "passive"))
    )
    (net (code "81") (name "unconnected-(U3-NC-Pad4)") (class "Default")
      (node (ref "U3") (pin "4") (pinfunction "NC_4") (pintype "passive"))
    )
    (net (code "82") (name "unconnected-(X1-NC-Pad22)") (class "Default")
      (node (ref "X1") (pin "22") (pinfunction "NC_22") (pintype "passive+no_connect"))
    )
    (net (code "83") (name "unconnected-(X2-1.28\"_TFT_LCD_ROUND-Pad1)") (class "Default")
      (node (ref "X2") (pin "1") (pinfunction "1.28\"_TFT_LCD_ROUND_1") (pintype "passive"))
    )
  )
)
